# MLX90393_breakout1_long.net
KiCad netlist of a schematic drawn in EAGLE
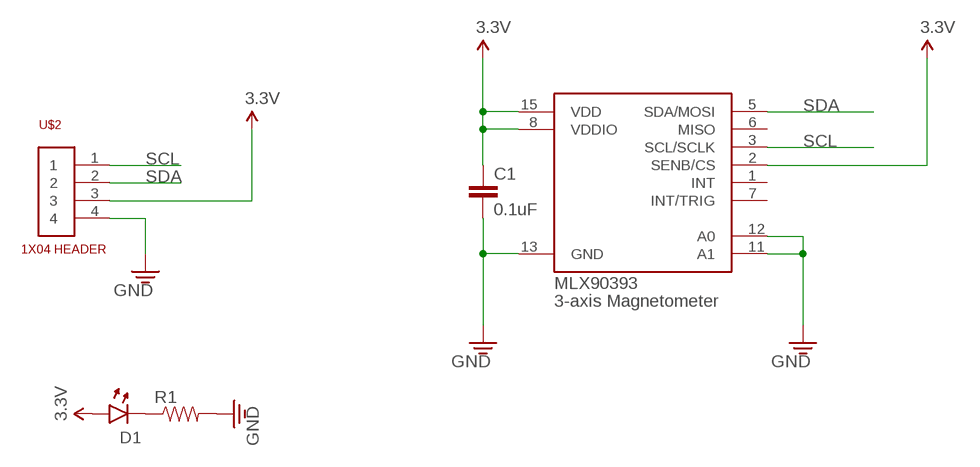
[diagram p0: schematic, sheet 1]

(export (version "E")
  (design (tool "Eeschema 10.0.6"))
  (components
    (comp (ref "C1")
      (value "0.1uF")
      (footprint "eagle-import:0603")
      (libsource (lib "eagle-import") (part "CAP0603"))
    )
    (comp (ref "D1")
      (value "0605-LED")
      (footprint "eagle-import:0603-LED")
      (libsource (lib "eagle-import") (part "0605-LED"))
    )
    (comp (ref "R1")
      (value "RESISTOR0603")
      (footprint "eagle-import:0603")
      (libsource (lib "eagle-import") (part "RESISTOR0603"))
    )
    (comp (ref "U$1")
      (value "MLX90393")
      (footprint "eagle-import:16-QFN")
      (libsource (lib "eagle-import") (part "MLX90393"))
    )
    (comp (ref "U$2")
      (value "1X04")
      (footprint "eagle-import:1X04")
      (libsource (lib "eagle-import") (part "1X04"))
    )
  )
  (nets
    (net (code "1") (name "/SCL") (class "Default")
      (node (ref "U$1") (pin "3") (pinfunction "SCL/SCLK_3") (pintype "bidirectional"))
      (node (ref "U$2") (pin "1") (pinfunction "1_1") (pintype "bidirectional"))
    )
    (net (code "2") (name "/SDA") (class "Default")
      (node (ref "U$1") (pin "5") (pinfunction "SDA/MOSI_5") (pintype "bidirectional"))
      (node (ref "U$2") (pin "2") (pinfunction "2_2") (pintype "bidirectional"))
    )
    (net (code "3") (name "3.3V") (class "Default")
      (node (ref "C1") (pin "1") (pinfunction "1_1") (pintype "passive"))
      (node (ref "D1") (pin "ANODE") (pinfunction "ANODE_ANODE") (pintype "bidirectional"))
      (node (ref "U$1") (pin "15") (pinfunction "VDD_15") (pintype "bidirectional"))
      (node (ref "U$1") (pin "2") (pinfunction "SENB/CS_2") (pintype "bidirectional"))
      (node (ref "U$1") (pin "8") (pinfunction "VDDIO_8") (pintype "bidirectional"))
      (node (ref "U$2") (pin "3") (pinfunction "3_3") (pintype "bidirectional"))
    )
    (net (code "4") (name "GND") (class "Default")
      (node (ref "C1") (pin "2") (pinfunction "2_2") (pintype "passive"))
      (node (ref "R1") (pin "2") (pinfunction "2_2") (pintype "passive"))
      (node (ref "U$1") (pin "11") (pinfunction "A1_11") (pintype "bidirectional"))
      (node (ref "U$1") (pin "12") (pinfunction "A0_12") (pintype "bidirectional"))
      (node (ref "U$1") (pin "13") (pinfunction "GND_13") (pintype "bidirectional"))
      (node (ref "U$2") (pin "4") (pinfunction "4_4") (pintype "bidirectional"))
    )
    (net (code "5") (name "Net-(D1-PadCATHODE)") (class "Default")
      (node (ref "D1") (pin "CATHODE") (pinfunction "CATHODE_CATHODE") (pintype "bidirectional"))
      (node (ref "R1") (pin "1") (pinfunction "1_1") (pintype "passive"))
    )
    (net (code "6") (name "unconnected-(U$1-INT-Pad1)") (class "Default")
      (node (ref "U$1") (pin "1") (pinfunction "INT_1") (pintype "bidirectional"))
    )
    (net (code "7") (name "unconnected-(U$1-INT{slash}TRIG-Pad7)") (class "Default")
      (node (ref "U$1") (pin "7") (pinfunction "INT/TRIG_7") (pintype "bidirectional"))
    )
    (net (code "8") (name "unconnected-(U$1-MISO-Pad6)") (class "Default")
      (node (ref "U$1") (pin "6") (pinfunction "MISO_6") (pintype "bidirectional"))
    )
  )
)
